# RiskChemi_Sensors_V2_03.net
KiCad netlist of a schematic drawn in Altium Designer
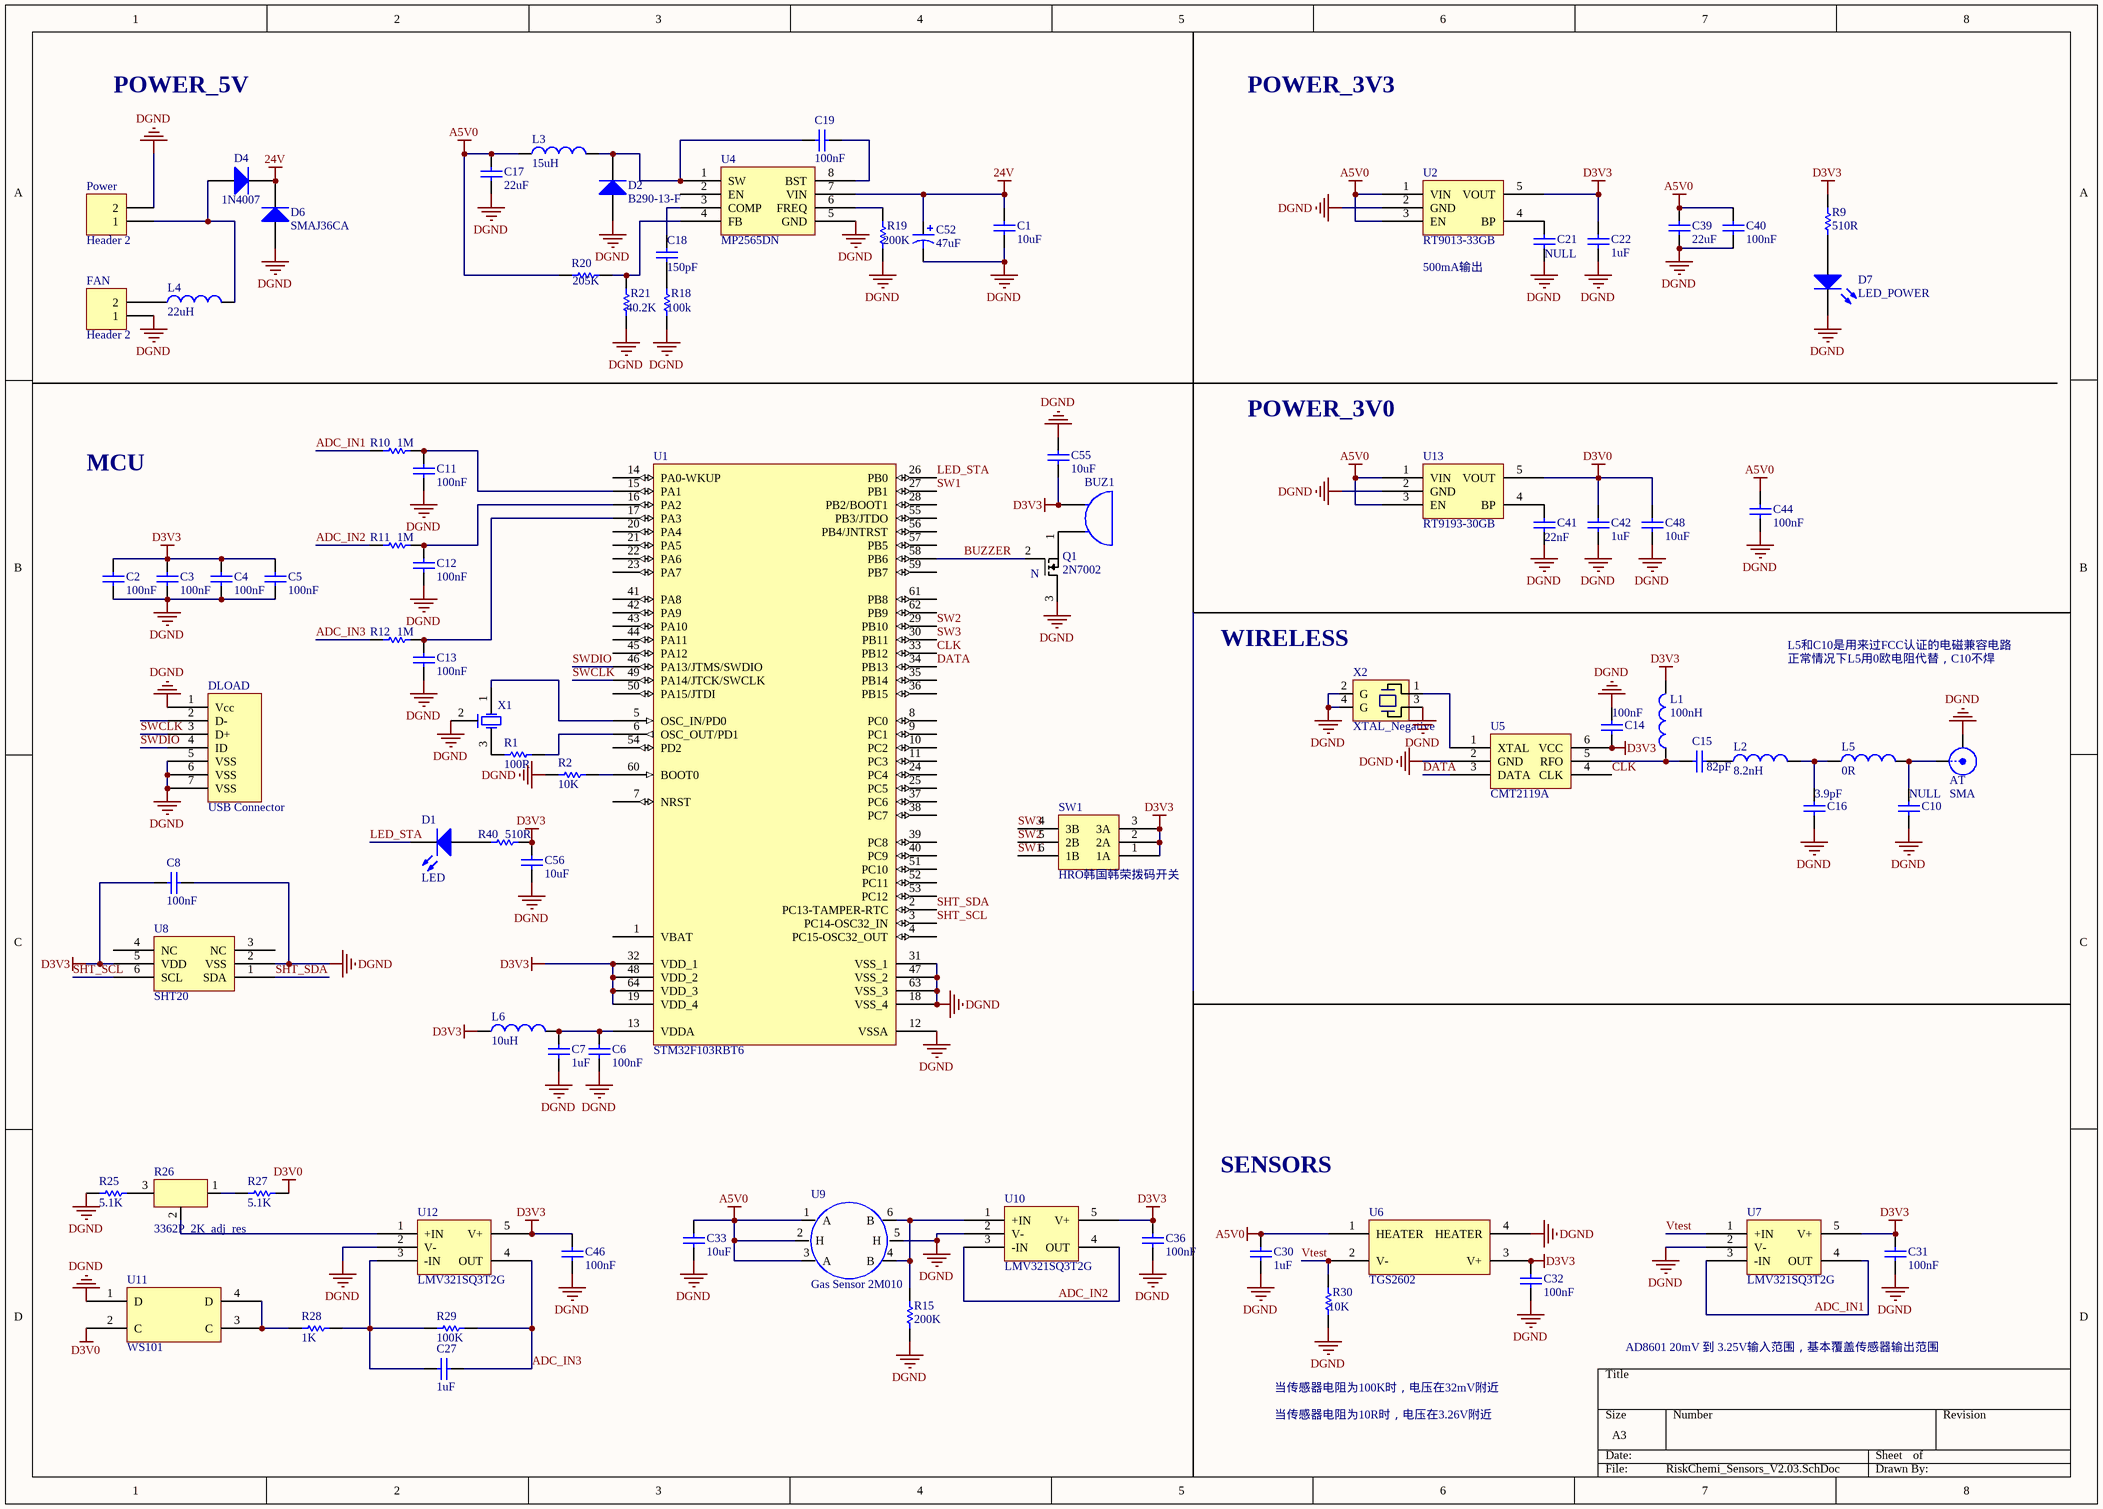
[diagram p0: RiskChemi_Sensors_V2.03.SchDoc]

(export (version "E")
  (design (tool "Eeschema 10.0.6"))
  (components
    (comp (ref "AT")
      (value "SMA")
      (footprint "SMA")
      (description "SMB Straight Connector")
      (fields (field (name "PUBLISHER") "Altium Limited"))
      (libsource (lib "Miscellaneous Connectors") (part "SMB"))
    )
    (comp (ref "BUZ1")
      (value "BUZZER 0905 through hole")
      (footprint "BUZ0905")
      (description "Buzzer")
      (libsource (lib "杂元件库") (part "BUZZER"))
    )
    (comp (ref "C1")
      (value "10uF")
      (footprint "0805")
      (description "Capacitor,50V")
      (fields (field (name "PUBLISHER") "Altium Limited"))
      (libsource (lib "Miscellaneous Devices") (part "Cap"))
    )
    (comp (ref "C2")
      (value "100nF")
      (footprint "BinFeng:0603")
      (description "Capacitor")
      (fields (field (name "PUBLISHER") "Altium Limited"))
      (libsource (lib "Miscellaneous Devices") (part "Cap"))
    )
    (comp (ref "C3")
      (value "100nF")
      (footprint "BinFeng:0603")
      (description "Capacitor")
      (fields (field (name "PUBLISHER") "Altium Limited"))
      (libsource (lib "Miscellaneous Devices") (part "Cap"))
    )
    (comp (ref "C4")
      (value "100nF")
      (footprint "BinFeng:0603")
      (description "Capacitor")
      (fields (field (name "PUBLISHER") "Altium Limited"))
      (libsource (lib "Miscellaneous Devices") (part "Cap"))
    )
    (comp (ref "C5")
      (value "100nF")
      (footprint "BinFeng:0603")
      (description "Capacitor")
      (fields (field (name "PUBLISHER") "Altium Limited"))
      (libsource (lib "Miscellaneous Devices") (part "Cap"))
    )
    (comp (ref "C6")
      (value "100nF")
      (footprint "BinFeng:0603")
      (description "Capacitor")
      (fields (field (name "PUBLISHER") "Altium Limited"))
      (libsource (lib "Miscellaneous Devices") (part "Cap"))
    )
    (comp (ref "C7")
      (value "1uF")
      (footprint "BinFeng:0603")
      (description "Capacitor")
      (fields (field (name "PUBLISHER") "Altium Limited"))
      (libsource (lib "Miscellaneous Devices") (part "Cap"))
    )
    (comp (ref "C8")
      (value "100nF")
      (footprint "BinFeng:0603")
      (description "Capacitor")
      (fields (field (name "PUBLISHER") "Altium Limited"))
      (libsource (lib "Miscellaneous Devices") (part "Cap"))
    )
    (comp (ref "C10")
      (value "NULL")
      (footprint "BinFeng:0402")
      (description "Capacitor")
      (fields (field (name "PUBLISHER") "Altium Limited"))
      (libsource (lib "Miscellaneous Devices") (part "Cap"))
    )
    (comp (ref "C11")
      (value "100nF")
      (footprint "BinFeng:0603")
      (description "Capacitor")
      (fields (field (name "PUBLISHER") "Altium Limited"))
      (libsource (lib "Miscellaneous Devices") (part "Cap"))
    )
    (comp (ref "C12")
      (value "100nF")
      (footprint "BinFeng:0603")
      (description "Capacitor")
      (fields (field (name "PUBLISHER") "Altium Limited"))
      (libsource (lib "Miscellaneous Devices") (part "Cap"))
    )
    (comp (ref "C13")
      (value "100nF")
      (footprint "BinFeng:0603")
      (description "Capacitor")
      (fields (field (name "PUBLISHER") "Altium Limited"))
      (libsource (lib "Miscellaneous Devices") (part "Cap"))
    )
    (comp (ref "C14")
      (value "100nF")
      (footprint "BinFeng:0402")
      (description "Capacitor")
      (fields (field (name "PUBLISHER") "Altium Limited"))
      (libsource (lib "Miscellaneous Devices") (part "Cap"))
    )
    (comp (ref "C15")
      (value "82pF")
      (footprint "BinFeng:0402")
      (description "Capacitor")
      (fields (field (name "PUBLISHER") "Altium Limited"))
      (libsource (lib "Miscellaneous Devices") (part "Cap"))
    )
    (comp (ref "C16")
      (value "3.9pF")
      (footprint "BinFeng:0402")
      (description "Capacitor")
      (fields (field (name "PUBLISHER") "Altium Limited"))
      (libsource (lib "Miscellaneous Devices") (part "Cap"))
    )
    (comp (ref "C17")
      (value "22uF")
      (footprint "0805")
      (description "Capacitor,50V")
      (fields (field (name "PUBLISHER") "Altium Limited"))
      (libsource (lib "Miscellaneous Devices") (part "Cap"))
    )
    (comp (ref "C18")
      (value "150pF")
      (footprint "BinFeng:0603")
      (description "Capacitor")
      (fields (field (name "PUBLISHER") "Altium Limited"))
      (libsource (lib "Miscellaneous Devices") (part "Cap"))
    )
    (comp (ref "C19")
      (value "100nF")
      (footprint "BinFeng:0603")
      (description "Capacitor")
      (fields (field (name "PUBLISHER") "Altium Limited"))
      (libsource (lib "Miscellaneous Devices") (part "Cap"))
    )
    (comp (ref "C21")
      (value "NULL")
      (footprint "BinFeng:0402")
      (description "Capacitor")
      (fields (field (name "PUBLISHER") "Altium Limited"))
      (libsource (lib "Miscellaneous Devices") (part "Cap"))
    )
    (comp (ref "C22")
      (value "1uF")
      (footprint "BinFeng:0402")
      (description "Capacitor")
      (fields (field (name "PUBLISHER") "Altium Limited"))
      (libsource (lib "Miscellaneous Devices") (part "Cap"))
    )
    (comp (ref "C27")
      (value "1uF")
      (footprint "BinFeng:0603")
      (description "Capacitor")
      (fields (field (name "PUBLISHER") "Altium Limited"))
      (libsource (lib "Miscellaneous Devices") (part "Cap"))
    )
    (comp (ref "C30")
      (value "1uF")
      (footprint "BinFeng:0603")
      (description "Capacitor")
      (fields (field (name "PUBLISHER") "Altium Limited"))
      (libsource (lib "Miscellaneous Devices") (part "Cap"))
    )
    (comp (ref "C31")
      (value "100nF")
      (footprint "BinFeng:0603")
      (description "Capacitor")
      (fields (field (name "PUBLISHER") "Altium Limited"))
      (libsource (lib "Miscellaneous Devices") (part "Cap"))
    )
    (comp (ref "C32")
      (value "100nF")
      (footprint "BinFeng:0603")
      (description "Capacitor")
      (fields (field (name "PUBLISHER") "Altium Limited"))
      (libsource (lib "Miscellaneous Devices") (part "Cap"))
    )
    (comp (ref "C33")
      (value "10uF")
      (footprint "0805")
      (description "Capacitor")
      (fields (field (name "PUBLISHER") "Altium Limited"))
      (libsource (lib "Miscellaneous Devices") (part "Cap"))
    )
    (comp (ref "C36")
      (value "100nF")
      (footprint "BinFeng:0603")
      (description "Capacitor")
      (fields (field (name "PUBLISHER") "Altium Limited"))
      (libsource (lib "Miscellaneous Devices") (part "Cap"))
    )
    (comp (ref "C39")
      (value "22uF")
      (footprint "1206")
      (description "Capacitor")
      (fields (field (name "PUBLISHER") "Altium Limited"))
      (libsource (lib "Miscellaneous Devices") (part "Cap"))
    )
    (comp (ref "C40")
      (value "100nF")
      (footprint "BinFeng:0402")
      (description "Capacitor")
      (fields (field (name "PUBLISHER") "Altium Limited"))
      (libsource (lib "Miscellaneous Devices") (part "Cap"))
    )
    (comp (ref "C41")
      (value "22nF")
      (footprint "BinFeng:0402")
      (description "Capacitor")
      (fields (field (name "PUBLISHER") "Altium Limited"))
      (libsource (lib "Miscellaneous Devices") (part "Cap"))
    )
    (comp (ref "C42")
      (value "1uF")
      (footprint "BinFeng:0402")
      (description "Capacitor")
      (fields (field (name "PUBLISHER") "Altium Limited"))
      (libsource (lib "Miscellaneous Devices") (part "Cap"))
    )
    (comp (ref "C44")
      (value "100nF")
      (footprint "BinFeng:0402")
      (description "Capacitor")
      (fields (field (name "PUBLISHER") "Altium Limited"))
      (libsource (lib "Miscellaneous Devices") (part "Cap"))
    )
    (comp (ref "C46")
      (value "100nF")
      (footprint "BinFeng:0603")
      (description "Capacitor")
      (fields (field (name "PUBLISHER") "Altium Limited"))
      (libsource (lib "Miscellaneous Devices") (part "Cap"))
    )
    (comp (ref "C48")
      (value "10uF")
      (footprint "0805")
      (description "Capacitor")
      (fields (field (name "PUBLISHER") "Altium Limited"))
      (libsource (lib "Miscellaneous Devices") (part "Cap"))
    )
    (comp (ref "C52")
      (value "47uF")
      (footprint "cap_pol_8*10.2")
      (description "Polarized Capacitor (Radial)")
      (fields (field (name "PUBLISHER") "Altium Limited"))
      (libsource (lib "Miscellaneous Devices") (part "Cap Pol1"))
    )
    (comp (ref "C55")
      (value "10uF")
      (footprint "0805")
      (description "Capacitor")
      (fields (field (name "PUBLISHER") "Altium Limited"))
      (libsource (lib "Miscellaneous Devices") (part "Cap"))
    )
    (comp (ref "C56")
      (value "10uF")
      (footprint "0805")
      (description "Capacitor")
      (fields (field (name "PUBLISHER") "Altium Limited"))
      (libsource (lib "Miscellaneous Devices") (part "Cap"))
    )
    (comp (ref "D1")
      (value "LED")
      (footprint "1206_LED")
      (description "Typical INFRARED GaAs LED")
      (fields (field (name "PUBLISHER") "Altium Limited"))
      (libsource (lib "Miscellaneous Devices") (part "LED0"))
    )
    (comp (ref "D2")
      (value "B290-13-F")
      (footprint "B290")
      (description "Default Diode")
      (fields (field (name "PUBLISHER") "Altium Limited"))
      (libsource (lib "Miscellaneous Devices") (part "Diode"))
    )
    (comp (ref "D4")
      (value "1N4007")
      (footprint "6032_pol")
      (description "1 Amp General Purpose Rectifier")
      (fields (field (name "PUBLISHER") "Altium Limited"))
      (libsource (lib "Miscellaneous Devices") (part "Diode 1N4007"))
    )
    (comp (ref "D6")
      (value "SMAJ36CA")
      (footprint "B290")
      (description "1 Amp General Purpose Rectifier")
      (fields (field (name "PUBLISHER") "Altium Limited"))
      (libsource (lib "Miscellaneous Devices") (part "Diode 1N4007"))
    )
    (comp (ref "D7")
      (value "LED_POWER")
      (footprint "1206_LED")
      (description "Typical INFRARED GaAs LED")
      (fields (field (name "PUBLISHER") "Altium Limited"))
      (libsource (lib "Miscellaneous Devices") (part "LED0"))
    )
    (comp (ref "DLOAD")
      (value "USB Connector")
      (footprint "Mini_USB")
      (libsource (lib "BinFeng_Connectors") (part "Component_1"))
    )
    (comp (ref "FAN")
      (value "Header 2")
      (footprint "HDR1X2")
      (description "Header, 2-Pin")
      (fields (field (name "PUBLISHER") "Altium Limited"))
      (libsource (lib "Miscellaneous Connectors") (part "Header 2"))
    )
    (comp (ref "L1")
      (value "100nH")
      (footprint "0603C")
      (description "Inductor")
      (fields (field (name "PUBLISHER") "Altium Limited"))
      (libsource (lib "Miscellaneous Devices") (part "Inductor"))
    )
    (comp (ref "L2")
      (value "8.2nH")
      (footprint "0603C")
      (description "Inductor")
      (fields (field (name "PUBLISHER") "Altium Limited"))
      (libsource (lib "Miscellaneous Devices") (part "Inductor"))
    )
    (comp (ref "L3")
      (value "15uH")
      (footprint "4*4 Inductor")
      (description "Inductor, 1A")
      (fields (field (name "PUBLISHER") "Altium Limited"))
      (libsource (lib "Miscellaneous Devices") (part "Inductor"))
    )
    (comp (ref "L4")
      (value "22uH")
      (footprint "10*10Inductor")
      (description "Inductor, 1A")
      (fields (field (name "PUBLISHER") "Altium Limited"))
      (libsource (lib "Miscellaneous Devices") (part "Inductor"))
    )
    (comp (ref "L5")
      (value "0R")
      (footprint "0603C")
      (description "Inductor")
      (fields (field (name "PUBLISHER") "Altium Limited"))
      (libsource (lib "Miscellaneous Devices") (part "Inductor"))
    )
    (comp (ref "L6")
      (value "10uH")
      (footprint "0805")
      (description "Inductor")
      (fields (field (name "PUBLISHER") "Altium Limited"))
      (libsource (lib "Miscellaneous Devices") (part "Inductor"))
    )
    (comp (ref "Power")
      (value "Header 2")
      (footprint "HDR1X2")
      (description "Header, 2-Pin")
      (fields (field (name "PUBLISHER") "Altium Limited"))
      (libsource (lib "Miscellaneous Connectors") (part "Header 2"))
    )
    (comp (ref "Q1") (value "2N7002") (footprint "2N7002") (libsource (lib "seeder") (part "N-MOSFET")))
    (comp (ref "R1")
      (value "100R")
      (footprint "BinFeng:0603")
      (description "Resistor")
      (fields (field (name "PUBLISHER") "Altium Limited"))
      (libsource (lib "Miscellaneous Devices") (part "Res1"))
    )
    (comp (ref "R2")
      (value "10K")
      (footprint "BinFeng:0603")
      (description "Resistor")
      (fields (field (name "PUBLISHER") "Altium Limited"))
      (libsource (lib "Miscellaneous Devices") (part "Res1"))
    )
    (comp (ref "R9")
      (value "510R")
      (footprint "BinFeng:0603")
      (description "Resistor")
      (fields (field (name "PUBLISHER") "Altium Limited"))
      (libsource (lib "Miscellaneous Devices") (part "Res1"))
    )
    (comp (ref "R10")
      (value "1M")
      (footprint "BinFeng:0603")
      (description "Resistor")
      (fields (field (name "PUBLISHER") "Altium Limited"))
      (libsource (lib "Miscellaneous Devices") (part "Res1"))
    )
    (comp (ref "R11")
      (value "1M")
      (footprint "BinFeng:0603")
      (description "Resistor")
      (fields (field (name "PUBLISHER") "Altium Limited"))
      (libsource (lib "Miscellaneous Devices") (part "Res1"))
    )
    (comp (ref "R12")
      (value "1M")
      (footprint "BinFeng:0603")
      (description "Resistor")
      (fields (field (name "PUBLISHER") "Altium Limited"))
      (libsource (lib "Miscellaneous Devices") (part "Res1"))
    )
    (comp (ref "R15")
      (value "200K")
      (footprint "BinFeng:0603C")
      (description "Resistor")
      (fields (field (name "Comment") "Res1") (field (name "PUBLISHER") "Altium Limited"))
      (libsource (lib "Miscellaneous Devices") (part "Res1"))
    )
    (comp (ref "R18")
      (value "100k")
      (footprint "BinFeng:0603")
      (description "Resistor")
      (fields (field (name "PUBLISHER") "Altium Limited"))
      (libsource (lib "Miscellaneous Devices") (part "Res1"))
    )
    (comp (ref "R19")
      (value "200K")
      (footprint "BinFeng:0402")
      (description "Resistor")
      (fields (field (name "PUBLISHER") "Altium Limited"))
      (libsource (lib "Miscellaneous Devices") (part "Res1"))
    )
    (comp (ref "R20")
      (value "205K")
      (footprint "BinFeng:0603")
      (description "Resistor")
      (fields (field (name "PUBLISHER") "Altium Limited"))
      (libsource (lib "Miscellaneous Devices") (part "Res1"))
    )
    (comp (ref "R21")
      (value "40.2K")
      (footprint "BinFeng:0603")
      (description "Resistor")
      (fields (field (name "PUBLISHER") "Altium Limited"))
      (libsource (lib "Miscellaneous Devices") (part "Res1"))
    )
    (comp (ref "R25")
      (value "5.1K")
      (footprint "BinFeng:0603")
      (description "Resistor")
      (fields (field (name "PUBLISHER") "Altium Limited"))
      (libsource (lib "Miscellaneous Devices") (part "Res1"))
    )
    (comp (ref "R26")
      (value "3362P_2K_adj_res")
      (footprint "res_adj")
      (libsource (lib "BinFeng_IC") (part "res_adj"))
    )
    (comp (ref "R27")
      (value "5.1K")
      (footprint "BinFeng:0603")
      (description "Resistor")
      (fields (field (name "PUBLISHER") "Altium Limited"))
      (libsource (lib "Miscellaneous Devices") (part "Res1"))
    )
    (comp (ref "R28")
      (value "1K")
      (footprint "BinFeng:0603")
      (description "Resistor")
      (fields (field (name "PUBLISHER") "Altium Limited"))
      (libsource (lib "Miscellaneous Devices") (part "Res1"))
    )
    (comp (ref "R29")
      (value "100K")
      (footprint "BinFeng:0603")
      (description "Resistor")
      (fields (field (name "PUBLISHER") "Altium Limited"))
      (libsource (lib "Miscellaneous Devices") (part "Res1"))
    )
    (comp (ref "R30")
      (value "10K")
      (footprint "BinFeng:0603")
      (description "Resistor")
      (fields (field (name "PUBLISHER") "Altium Limited"))
      (libsource (lib "Miscellaneous Devices") (part "Res1"))
    )
    (comp (ref "R40")
      (value "510R")
      (footprint "BinFeng:0603")
      (description "Resistor")
      (fields (field (name "PUBLISHER") "Altium Limited"))
      (libsource (lib "Miscellaneous Devices") (part "Res1"))
    )
    (comp (ref "SW1")
      (value "HRO韩国韩荣拨码开关")
      (footprint "SW_6P_HRO")
      (libsource (lib "BinFeng_IC") (part "SW_6P"))
    )
    (comp (ref "U1")
      (value "STM32F103RBT6")
      (footprint "LQFP64_N")
      (description "STM32 ARM-based 32-bit MCU with 64 Kbytes Flash, 64-pin LQFP, Industrial Temperature")
      (fields (field (name "PUBLISHER") "Altium Limited"))
      (libsource (lib "ST Microcontroller 32-Bit STM32") (part "STM32F103R8T6"))
    )
    (comp (ref "U2")
      (value "RT9013-33GB")
      (footprint "SOT-23-5")
      (libsource (lib "BinFeng_IC") (part "RT9193"))
    )
    (comp (ref "U4")
      (value "MP2565DN")
      (footprint "so-8")
      (description "DCDC 4.5V~28V input 1.8V ~5V output low power")
      (libsource (lib "BinFeng_IC") (part "MP1584"))
    )
    (comp (ref "U5")
      (value "CMT2119A")
      (footprint "sot23-6")
      (libsource (lib "BinFeng_IC") (part "CMT2119A"))
    )
    (comp (ref "U6")
      (value "TGS2602")
      (footprint "Gas Sensor TGS2602 Slot")
      (description "VOC sensor")
      (libsource (lib "BinFeng_IC") (part "TGS2602"))
    )
    (comp (ref "U7")
      (value "LMV321SQ3T2G")
      (footprint "SC-70-5")
      (libsource (lib "BinFeng_IC") (part "LMV321SQ3T2G"))
    )
    (comp (ref "U8") (value "SHT20") (footprint "SHT20") (libsource (lib "BinFeng_IC") (part "SHT20")))
    (comp (ref "U9")
      (value "Gas Sensor 2M010")
      (footprint "Gas Sensor 2M010 Slot")
      (libsource (lib "BinFeng_IC") (part "Gas Sensor"))
    )
    (comp (ref "U10")
      (value "LMV321SQ3T2G")
      (footprint "SC-70-5")
      (libsource (lib "BinFeng_IC") (part "LMV321SQ3T2G"))
    )
    (comp (ref "U11")
      (value "WS101")
      (footprint "Gas_Sensor_WS101_Slot")
      (libsource (lib "BinFeng_IC") (part "Gas Sensor_WS101"))
    )
    (comp (ref "U12")
      (value "LMV321SQ3T2G")
      (footprint "SC-70-5")
      (libsource (lib "BinFeng_IC") (part "LMV321SQ3T2G"))
    )
    (comp (ref "U13")
      (value "RT9193-30GB")
      (footprint "SOT-23-5")
      (libsource (lib "BinFeng_IC") (part "RT9193"))
    )
    (comp (ref "X1") (value "8M smd") (footprint "8Mhz_XTAL") (libsource (lib "Schlib1") (part "8M smd")))
    (comp (ref "X2")
      (value "XTAL_Negative")
      (footprint "XTAL3225")
      (libsource (lib "BinFeng_IC") (part "XTAL_Negative"))
    )
  )
  (nets
    (net (code "1") (name "/ADC_IN1") (class "Default")
      (node (ref "R10") (pin "1") (pinfunction "1_1") (pintype "passive"))
      (node (ref "U7") (pin "3") (pinfunction "-IN_3") (pintype "passive"))
      (node (ref "U7") (pin "4") (pinfunction "OUT_4") (pintype "passive"))
    )
    (net (code "2") (name "/ADC_IN2") (class "Default")
      (node (ref "R11") (pin "1") (pinfunction "1_1") (pintype "passive"))
      (node (ref "U10") (pin "3") (pinfunction "-IN_3") (pintype "passive"))
      (node (ref "U10") (pin "4") (pinfunction "OUT_4") (pintype "passive"))
    )
    (net (code "3") (name "/ADC_IN3") (class "Default")
      (node (ref "C27") (pin "1") (pinfunction "1_1") (pintype "passive"))
      (node (ref "R12") (pin "1") (pinfunction "1_1") (pintype "passive"))
      (node (ref "R29") (pin "2") (pinfunction "2_2") (pintype "passive"))
      (node (ref "U12") (pin "4") (pinfunction "OUT_4") (pintype "passive"))
    )
    (net (code "4") (name "/BUZZER") (class "Default")
      (node (ref "Q1") (pin "2") (pinfunction "G_2") (pintype "passive"))
      (node (ref "U1") (pin "58") (pinfunction "PB6_58") (pintype "bidirectional"))
    )
    (net (code "5") (name "/CLK") (class "Default")
      (node (ref "U1") (pin "33") (pinfunction "PB12_33") (pintype "bidirectional"))
      (node (ref "U5") (pin "4") (pinfunction "CLK_4") (pintype "passive"))
    )
    (net (code "6") (name "/DATA") (class "Default")
      (node (ref "U1") (pin "34") (pinfunction "PB13_34") (pintype "bidirectional"))
      (node (ref "U5") (pin "3") (pinfunction "DATA_3") (pintype "passive"))
    )
    (net (code "7") (name "/LED_STA") (class "Default")
      (node (ref "D1") (pin "2") (pinfunction "K_2") (pintype "passive"))
      (node (ref "U1") (pin "26") (pinfunction "PB0_26") (pintype "bidirectional"))
    )
    (net (code "8") (name "/SHT_SCL") (class "Default")
      (node (ref "U1") (pin "3") (pinfunction "PC14-OSC32_IN_3") (pintype "bidirectional"))
      (node (ref "U8") (pin "6") (pinfunction "SCL_6") (pintype "passive"))
    )
    (net (code "9") (name "/SHT_SDA") (class "Default")
      (node (ref "U1") (pin "2") (pinfunction "PC13-TAMPER-RTC_2") (pintype "bidirectional"))
      (node (ref "U8") (pin "1") (pinfunction "SDA_1") (pintype "passive"))
    )
    (net (code "10") (name "/SW1") (class "Default")
      (node (ref "SW1") (pin "6") (pinfunction "1B_6") (pintype "passive"))
      (node (ref "U1") (pin "27") (pinfunction "PB1_27") (pintype "bidirectional"))
    )
    (net (code "11") (name "/SW2") (class "Default")
      (node (ref "SW1") (pin "5") (pinfunction "2B_5") (pintype "passive"))
      (node (ref "U1") (pin "29") (pinfunction "PB10_29") (pintype "bidirectional"))
    )
    (net (code "12") (name "/SW3") (class "Default")
      (node (ref "SW1") (pin "4") (pinfunction "3B_4") (pintype "passive"))
      (node (ref "U1") (pin "30") (pinfunction "PB11_30") (pintype "bidirectional"))
    )
    (net (code "13") (name "/SWCLK") (class "Default")
      (node (ref "DLOAD") (pin "3") (pinfunction "D+_3") (pintype "passive"))
      (node (ref "U1") (pin "49") (pinfunction "PA14/JTCK/SWCLK_49") (pintype "bidirectional"))
    )
    (net (code "14") (name "/SWDIO") (class "Default")
      (node (ref "DLOAD") (pin "4") (pinfunction "ID_4") (pintype "passive"))
      (node (ref "U1") (pin "46") (pinfunction "PA13/JTMS/SWDIO_46") (pintype "bidirectional"))
    )
    (net (code "15") (name "/Vtest") (class "Default")
      (node (ref "R30") (pin "2") (pinfunction "2_2") (pintype "passive"))
      (node (ref "U6") (pin "2") (pinfunction "V-_2") (pintype "passive"))
      (node (ref "U7") (pin "1") (pinfunction "+IN_1") (pintype "passive"))
    )
    (net (code "16") (name "24V") (class "Default")
      (node (ref "C1") (pin "2") (pinfunction "2_2") (pintype "passive"))
      (node (ref "C52") (pin "1") (pinfunction "1_1") (pintype "passive"))
      (node (ref "D4") (pin "2") (pinfunction "K_2") (pintype "passive"))
      (node (ref "D6") (pin "2") (pinfunction "K_2") (pintype "passive"))
      (node (ref "U4") (pin "7") (pinfunction "VIN_7") (pintype "passive"))
    )
    (net (code "17") (name "A5V0") (class "Default")
      (node (ref "C17") (pin "2") (pinfunction "2_2") (pintype "passive"))
      (node (ref "C30") (pin "2") (pinfunction "2_2") (pintype "passive"))
      (node (ref "C33") (pin "2") (pinfunction "2_2") (pintype "passive"))
      (node (ref "C39") (pin "1") (pinfunction "1_1") (pintype "passive"))
      (node (ref "C40") (pin "2") (pinfunction "2_2") (pintype "passive"))
      (node (ref "C44") (pin "2") (pinfunction "2_2") (pintype "passive"))
      (node (ref "L3") (pin "1") (pinfunction "1_1") (pintype "passive"))
      (node (ref "R20") (pin "2") (pinfunction "2_2") (pintype "passive"))
      (node (ref "U13") (pin "1") (pinfunction "VIN_1") (pintype "passive"))
      (node (ref "U13") (pin "3") (pinfunction "EN_3") (pintype "passive"))
      (node (ref "U2") (pin "1") (pinfunction "VIN_1") (pintype "passive"))
      (node (ref "U2") (pin "3") (pinfunction "EN_3") (pintype "passive"))
      (node (ref "U6") (pin "1") (pinfunction "HEATER_1") (pintype "passive"))
      (node (ref "U9") (pin "1") (pinfunction "A_1") (pintype "passive"))
      (node (ref "U9") (pin "2") (pinfunction "H_2") (pintype "passive"))
      (node (ref "U9") (pin "3") (pinfunction "A_3") (pintype "passive"))
    )
    (net (code "18") (name "D3V0") (class "Default")
      (node (ref "C42") (pin "2") (pinfunction "2_2") (pintype "passive"))
      (node (ref "C48") (pin "2") (pinfunction "2_2") (pintype "passive"))
      (node (ref "R27") (pin "2") (pinfunction "2_2") (pintype "passive"))
      (node (ref "U11") (pin "2") (pinfunction "C_2") (pintype "passive"))
      (node (ref "U13") (pin "5") (pinfunction "VOUT_5") (pintype "passive"))
    )
    (net (code "19") (name "D3V3") (class "Default")
      (node (ref "BUZ1") (pin "1") (pinfunction "A_1") (pintype "passive"))
      (node (ref "C14") (pin "2") (pinfunction "2_2") (pintype "passive"))
      (node (ref "C2") (pin "2") (pinfunction "2_2") (pintype "passive"))
      (node (ref "C22") (pin "2") (pinfunction "2_2") (pintype "passive"))
      (node (ref "C3") (pin "2") (pinfunction "2_2") (pintype "passive"))
      (node (ref "C31") (pin "2") (pinfunction "2_2") (pintype "passive"))
      (node (ref "C32") (pin "2") (pinfunction "2_2") (pintype "passive"))
      (node (ref "C36") (pin "2") (pinfunction "2_2") (pintype "passive"))
      (node (ref "C4") (pin "2") (pinfunction "2_2") (pintype "passive"))
      (node (ref "C46") (pin "2") (pinfunction "2_2") (pintype "passive"))
      (node (ref "C5") (pin "2") (pinfunction "2_2") (pintype "passive"))
      (node (ref "C55") (pin "2") (pinfunction "2_2") (pintype "passive"))
      (node (ref "C56") (pin "2") (pinfunction "2_2") (pintype "passive"))
      (node (ref "C8") (pin "2") (pinfunction "2_2") (pintype "passive"))
      (node (ref "L1") (pin "2") (pinfunction "2_2") (pintype "passive"))
      (node (ref "L6") (pin "1") (pinfunction "1_1") (pintype "passive"))
      (node (ref "R40") (pin "2") (pinfunction "2_2") (pintype "passive"))
      (node (ref "R9") (pin "2") (pinfunction "2_2") (pintype "passive"))
      (node (ref "SW1") (pin "1") (pinfunction "1A_1") (pintype "passive"))
      (node (ref "SW1") (pin "2") (pinfunction "2A_2") (pintype "passive"))
      (node (ref "SW1") (pin "3") (pinfunction "3A_3") (pintype "passive"))
      (node (ref "U1") (pin "19") (pinfunction "VDD_4_19") (pintype "power_in"))
      (node (ref "U1") (pin "32") (pinfunction "VDD_1_32") (pintype "power_in"))
      (node (ref "U1") (pin "48") (pinfunction "VDD_2_48") (pintype "power_in"))
      (node (ref "U1") (pin "64") (pinfunction "VDD_3_64") (pintype "power_in"))
      (node (ref "U10") (pin "5") (pinfunction "V+_5") (pintype "passive"))
      (node (ref "U12") (pin "5") (pinfunction "V+_5") (pintype "passive"))
      (node (ref "U2") (pin "5") (pinfunction "VOUT_5") (pintype "passive"))
      (node (ref "U5") (pin "6") (pinfunction "VCC_6") (pintype "passive"))
      (node (ref "U6") (pin "3") (pinfunction "V+_3") (pintype "passive"))
      (node (ref "U7") (pin "5") (pinfunction "V+_5") (pintype "passive"))
      (node (ref "U8") (pin "5") (pinfunction "VDD_5") (pintype "passive"))
    )
    (net (code "20") (name "DGND") (class "Default")
      (node (ref "AT") (pin "2") (pinfunction "Y_2") (pintype "passive"))
      (node (ref "C1") (pin "1") (pinfunction "1_1") (pintype "passive"))
      (node (ref "C10") (pin "1") (pinfunction "1_1") (pintype "passive"))
      (node (ref "C11") (pin "2") (pinfunction "2_2") (pintype "passive"))
      (node (ref "C12") (pin "1") (pinfunction "1_1") (pintype "passive"))
      (node (ref "C13") (pin "1") (pinfunction "1_1") (pintype "passive"))
      (node (ref "C14") (pin "1") (pinfunction "1_1") (pintype "passive"))
      (node (ref "C16") (pin "1") (pinfunction "1_1") (pintype "passive"))
      (node (ref "C17") (pin "1") (pinfunction "1_1") (pintype "passive"))
      (node (ref "C2") (pin "1") (pinfunction "1_1") (pintype "passive"))
      (node (ref "C21") (pin "1") (pinfunction "1_1") (pintype "passive"))
      (node (ref "C22") (pin "1") (pinfunction "1_1") (pintype "passive"))
      (node (ref "C3") (pin "1") (pinfunction "1_1") (pintype "passive"))
      (node (ref "C30") (pin "1") (pinfunction "1_1") (pintype "passive"))
      (node (ref "C31") (pin "1") (pinfunction "1_1") (pintype "passive"))
      (node (ref "C32") (pin "1") (pinfunction "1_1") (pintype "passive"))
      (node (ref "C33") (pin "1") (pinfunction "1_1") (pintype "passive"))
      (node (ref "C36") (pin "1") (pinfunction "1_1") (pintype "passive"))
      (node (ref "C39") (pin "2") (pinfunction "2_2") (pintype "passive"))
      (node (ref "C4") (pin "1") (pinfunction "1_1") (pintype "passive"))
      (node (ref "C40") (pin "1") (pinfunction "1_1") (pintype "passive"))
      (node (ref "C41") (pin "1") (pinfunction "1_1") (pintype "passive"))
      (node (ref "C42") (pin "1") (pinfunction "1_1") (pintype "passive"))
      (node (ref "C44") (pin "1") (pinfunction "1_1") (pintype "passive"))
      (node (ref "C46") (pin "1") (pinfunction "1_1") (pintype "passive"))
      (node (ref "C48") (pin "1") (pinfunction "1_1") (pintype "passive"))
      (node (ref "C5") (pin "1") (pinfunction "1_1") (pintype "passive"))
      (node (ref "C52") (pin "2") (pinfunction "2_2") (pintype "passive"))
      (node (ref "C55") (pin "1") (pinfunction "1_1") (pintype "passive"))
      (node (ref "C56") (pin "1") (pinfunction "1_1") (pintype "passive"))
      (node (ref "C6") (pin "1") (pinfunction "1_1") (pintype "passive"))
      (node (ref "C7") (pin "1") (pinfunction "1_1") (pintype "passive"))
      (node (ref "C8") (pin "1") (pinfunction "1_1") (pintype "passive"))
      (node (ref "D2") (pin "1") (pinfunction "A_1") (pintype "passive"))
      (node (ref "D6") (pin "1") (pinfunction "A_1") (pintype "passive"))
      (node (ref "D7") (pin "2") (pinfunction "K_2") (pintype "passive"))
      (node (ref "DLOAD") (pin "1") (pinfunction "Vcc_1") (pintype "passive"))
      (node (ref "DLOAD") (pin "5") (pinfunction "VSS_5") (pintype "passive"))
      (node (ref "DLOAD") (pin "6") (pinfunction "VSS_6") (pintype "passive"))
      (node (ref "DLOAD") (pin "7") (pinfunction "VSS_7") (pintype "passive"))
      (node (ref "FAN") (pin "1") (pinfunction "1_1") (pintype "passive"))
      (node (ref "Power") (pin "2") (pinfunction "2_2") (pintype "passive"))
      (node (ref "Q1") (pin "3") (pinfunction "S_3") (pintype "passive"))
      (node (ref "R15") (pin "2") (pinfunction "2_2") (pintype "passive"))
      (node (ref "R18") (pin "1") (pinfunction "1_1") (pintype "passive"))
      (node (ref "R19") (pin "1") (pinfunction "1_1") (pintype "passive"))
      (node (ref "R2") (pin "1") (pinfunction "1_1") (pintype "passive"))
      (node (ref "R21") (pin "1") (pinfunction "1_1") (pintype "passive"))
      (node (ref "R25") (pin "1") (pinfunction "1_1") (pintype "passive"))
      (node (ref "R30") (pin "1") (pinfunction "1_1") (pintype "passive"))
      (node (ref "U1") (pin "12") (pinfunction "VSSA_12") (pintype "power_in"))
      (node (ref "U1") (pin "18") (pinfunction "VSS_4_18") (pintype "power_in"))
      (node (ref "U1") (pin "31") (pinfunction "VSS_1_31") (pintype "power_in"))
      (node (ref "U1") (pin "47") (pinfunction "VSS_2_47") (pintype "power_in"))
      (node (ref "U1") (pin "63") (pinfunction "VSS_3_63") (pintype "power_in"))
      (node (ref "U10") (pin "2") (pinfunction "V-_2") (pintype "passive"))
      (node (ref "U11") (pin "1") (pinfunction "D_1") (pintype "passive"))
      (node (ref "U12") (pin "2") (pinfunction "V-_2") (pintype "passive"))
      (node (ref "U13") (pin "2") (pinfunction "GND_2") (pintype "passive"))
      (node (ref "U2") (pin "2") (pinfunction "GND_2") (pintype "passive"))
      (node (ref "U4") (pin "5") (pinfunction "GND_5") (pintype "passive"))
      (node (ref "U5") (pin "2") (pinfunction "GND_2") (pintype "passive"))
      (node (ref "U6") (pin "4") (pinfunction "HEATER_4") (pintype "passive"))
      (node (ref "U7") (pin "2") (pinfunction "V-_2") (pintype "passive"))
      (node (ref "U8") (pin "2") (pinfunction "VSS_2") (pintype "passive"))
      (node (ref "U9") (pin "5") (pinfunction "H_5") (pintype "passive"))
      (node (ref "X1") (pin "2") (pinfunction "GND_2") (pintype "passive"))
      (node (ref "X2") (pin "2") (pinfunction "G_2") (pintype "passive"))
      (node (ref "X2") (pin "3") (pintype "passive"))
      (node (ref "X2") (pin "4") (pinfunction "G_4") (pintype "passive"))
    )
    (net (code "21") (name "Net-(AT-X)") (class "Default")
      (node (ref "AT") (pin "1") (pinfunction "X_1") (pintype "passive"))
      (node (ref "C10") (pin "2") (pinfunction "2_2") (pintype "passive"))
      (node (ref "L5") (pin "2") (pinfunction "2_2") (pintype "passive"))
    )
    (net (code "22") (name "Net-(BUZ1-B)") (class "Default")
      (node (ref "BUZ1") (pin "2") (pinfunction "B_2") (pintype "passive"))
      (node (ref "Q1") (pin "1") (pinfunction "D_1") (pintype "passive"))
    )
    (net (code "23") (name "Net-(C15-Pad2)") (class "Default")
      (node (ref "C15") (pin "2") (pinfunction "2_2") (pintype "passive"))
      (node (ref "L2") (pin "1") (pinfunction "1_1") (pintype "passive"))
    )
    (net (code "24") (name "Net-(C16-Pad2)") (class "Default")
      (node (ref "C16") (pin "2") (pinfunction "2_2") (pintype "passive"))
      (node (ref "L2") (pin "2") (pinfunction "2_2") (pintype "passive"))
      (node (ref "L5") (pin "1") (pinfunction "1_1") (pintype "passive"))
    )
    (net (code "25") (name "Net-(C18-Pad2)") (class "Default")
      (node (ref "C18") (pin "2") (pinfunction "2_2") (pintype "passive"))
      (node (ref "R18") (pin "2") (pinfunction "2_2") (pintype "passive"))
    )
    (net (code "26") (name "Net-(D1-A)") (class "Default")
      (node (ref "D1") (pin "1") (pinfunction "A_1") (pintype "passive"))
      (node (ref "R40") (pin "1") (pinfunction "1_1") (pintype "passive"))
    )
    (net (code "27") (name "Net-(D2-K)") (class "Default")
      (node (ref "C19") (pin "2") (pinfunction "2_2") (pintype "passive"))
      (node (ref "D2") (pin "2") (pinfunction "K_2") (pintype "passive"))
      (node (ref "L3") (pin "2") (pinfunction "2_2") (pintype "passive"))
      (node (ref "U4") (pin "1") (pinfunction "SW_1") (pintype "passive"))
    )
    (net (code "28") (name "Net-(D4-A)") (class "Default")
      (node (ref "D4") (pin "1") (pinfunction "A_1") (pintype "passive"))
      (node (ref "L4") (pin "2") (pinfunction "2_2") (pintype "passive"))
      (node (ref "Power") (pin "1") (pinfunction "1_1") (pintype "passive"))
    )
    (net (code "29") (name "Net-(D7-A)") (class "Default")
      (node (ref "D7") (pin "1") (pinfunction "A_1") (pintype "passive"))
      (node (ref "R9") (pin "1") (pinfunction "1_1") (pintype "passive"))
    )
    (net (code "30") (name "Net-(FAN-Pad2)") (class "Default")
      (node (ref "FAN") (pin "2") (pinfunction "2_2") (pintype "passive"))
      (node (ref "L4") (pin "1") (pinfunction "1_1") (pintype "passive"))
    )
    (net (code "31") (name "Net-(R25-Pad2)") (class "Default")
      (node (ref "R25") (pin "2") (pinfunction "2_2") (pintype "passive"))
      (node (ref "R26") (pin "3") (pintype "passive"))
    )
    (net (code "32") (name "Net-(R26-Pad1)") (class "Default")
      (node (ref "R26") (pin "1") (pintype "passive"))
      (node (ref "R27") (pin "1") (pinfunction "1_1") (pintype "passive"))
    )
    (net (code "33") (name "Net-(R28-Pad1)") (class "Default")
      (node (ref "R28") (pin "1") (pinfunction "1_1") (pintype "passive"))
      (node (ref "U11") (pin "3") (pinfunction "C_3") (pintype "passive"))
      (node (ref "U11") (pin "4") (pinfunction "D_4") (pintype "passive"))
    )
    (net (code "34") (name "Net-(U1-BOOT0)") (class "Default")
      (node (ref "R2") (pin "2") (pinfunction "2_2") (pintype "passive"))
      (node (ref "U1") (pin "60") (pinfunction "BOOT0_60") (pintype "input"))
    )
    (net (code "35") (name "Net-(U1-OSC_IN{slash}PD0)") (class "Default")
      (node (ref "U1") (pin "5") (pinfunction "OSC_IN/PD0_5") (pintype "input"))
      (node (ref "X1") (pin "1") (pinfunction "OSC1_1") (pintype "passive"))
    )
    (net (code "36") (name "Net-(U1-OSC_OUT{slash}PD1)") (class "Default")
      (node (ref "R1") (pin "2") (pinfunction "2_2") (pintype "passive"))
      (node (ref "U1") (pin "6") (pinfunction "OSC_OUT/PD1_6") (pintype "output"))
    )
    (net (code "37") (name "Net-(U1-PA1)") (class "Default")
      (node (ref "C11") (pin "1") (pinfunction "1_1") (pintype "passive"))
      (node (ref "R10") (pin "2") (pinfunction "2_2") (pintype "passive"))
      (node (ref "U1") (pin "15") (pinfunction "PA1_15") (pintype "bidirectional"))
    )
    (net (code "38") (name "Net-(U1-PA2)") (class "Default")
      (node (ref "C12") (pin "2") (pinfunction "2_2") (pintype "passive"))
      (node (ref "R11") (pin "2") (pinfunction "2_2") (pintype "passive"))
      (node (ref "U1") (pin "16") (pinfunction "PA2_16") (pintype "bidirectional"))
    )
    (net (code "39") (name "Net-(U1-PA3)") (class "Default")
      (node (ref "C13") (pin "2") (pinfunction "2_2") (pintype "passive"))
      (node (ref "R12") (pin "2") (pinfunction "2_2") (pintype "passive"))
      (node (ref "U1") (pin "17") (pinfunction "PA3_17") (pintype "bidirectional"))
    )
    (net (code "40") (name "Net-(U1-VDDA)") (class "Default")
      (node (ref "C6") (pin "2") (pinfunction "2_2") (pintype "passive"))
      (node (ref "C7") (pin "2") (pinfunction "2_2") (pintype "passive"))
      (node (ref "L6") (pin "2") (pinfunction "2_2") (pintype "passive"))
      (node (ref "U1") (pin "13") (pinfunction "VDDA_13") (pintype "power_in"))
    )
    (net (code "41") (name "Net-(U2-BP)") (class "Default")
      (node (ref "C21") (pin "2") (pinfunction "2_2") (pintype "passive"))
      (node (ref "U2") (pin "4") (pinfunction "BP_4") (pintype "passive"))
    )
    (net (code "42") (name "Net-(U4-BST)") (class "Default")
      (node (ref "C19") (pin "1") (pinfunction "1_1") (pintype "passive"))
      (node (ref "U4") (pin "8") (pinfunction "BST_8") (pintype "passive"))
    )
    (net (code "43") (name "Net-(U4-COMP)") (class "Default")
      (node (ref "C18") (pin "1") (pinfunction "1_1") (pintype "passive"))
      (node (ref "U4") (pin "3") (pinfunction "COMP_3") (pintype "passive"))
    )
    (net (code "44") (name "Net-(U4-FB)") (class "Default")
      (node (ref "R20") (pin "1") (pinfunction "1_1") (pintype "passive"))
      (node (ref "R21") (pin "2") (pinfunction "2_2") (pintype "passive"))
      (node (ref "U4") (pin "4") (pinfunction "FB_4") (pintype "passive"))
    )
    (net (code "45") (name "Net-(U4-FREQ)") (class "Default")
      (node (ref "R19") (pin "2") (pinfunction "2_2") (pintype "passive"))
      (node (ref "U4") (pin "6") (pinfunction "FREQ_6") (pintype "passive"))
    )
    (net (code "46") (name "Net-(U5-RFO)") (class "Default")
      (node (ref "C15") (pin "1") (pinfunction "1_1") (pintype "passive"))
      (node (ref "L1") (pin "1") (pinfunction "1_1") (pintype "passive"))
      (node (ref "U5") (pin "5") (pinfunction "RFO_5") (pintype "passive"))
    )
    (net (code "47") (name "Net-(U5-XTAL)") (class "Default")
      (node (ref "U5") (pin "1") (pinfunction "XTAL_1") (pintype "passive"))
      (node (ref "X2") (pin "1") (pintype "passive"))
    )
    (net (code "48") (name "Net-(U10-+IN)") (class "Default")
      (node (ref "R15") (pin "1") (pinfunction "1_1") (pintype "passive"))
      (node (ref "U10") (pin "1") (pinfunction "+IN_1") (pintype "passive"))
      (node (ref "U9") (pin "4") (pinfunction "B_4") (pintype "passive"))
      (node (ref "U9") (pin "6") (pinfunction "B_6") (pintype "passive"))
    )
    (net (code "49") (name "Net-(U12-+IN)") (class "Default")
      (node (ref "R26") (pin "2") (pintype "passive"))
      (node (ref "U12") (pin "1") (pinfunction "+IN_1") (pintype "passive"))
    )
    (net (code "50") (name "Net-(U12--IN)") (class "Default")
      (node (ref "C27") (pin "2") (pinfunction "2_2") (pintype "passive"))
      (node (ref "R28") (pin "2") (pinfunction "2_2") (pintype "passive"))
      (node (ref "R29") (pin "1") (pinfunction "1_1") (pintype "passive"))
      (node (ref "U12") (pin "3") (pinfunction "-IN_3") (pintype "passive"))
    )
    (net (code "51") (name "Net-(U13-BP)") (class "Default")
      (node (ref "C41") (pin "2") (pinfunction "2_2") (pintype "passive"))
      (node (ref "U13") (pin "4") (pinfunction "BP_4") (pintype "passive"))
    )
    (net (code "52") (name "Net-(X1-OSC2)") (class "Default")
      (node (ref "R1") (pin "1") (pinfunction "1_1") (pintype "passive"))
      (node (ref "X1") (pin "3") (pinfunction "OSC2_3") (pintype "passive"))
    )
    (net (code "53") (name "unconnected-(DLOAD-D--Pad2)") (class "Default")
      (node (ref "DLOAD") (pin "2") (pinfunction "D-_2") (pintype "passive"))
    )
    (net (code "54") (name "unconnected-(U1-NRST-Pad7)") (class "Default")
      (node (ref "U1") (pin "7") (pinfunction "NRST_7") (pintype "bidirectional"))
    )
    (net (code "55") (name "unconnected-(U1-PA0-WKUP-Pad14)") (class "Default")
      (node (ref "U1") (pin "14") (pinfunction "PA0-WKUP_14") (pintype "bidirectional"))
    )
    (net (code "56") (name "unconnected-(U1-PA4-Pad20)") (class "Default")
      (node (ref "U1") (pin "20") (pinfunction "PA4_20") (pintype "bidirectional"))
    )
    (net (code "57") (name "unconnected-(U1-PA5-Pad21)") (class "Default")
      (node (ref "U1") (pin "21") (pinfunction "PA5_21") (pintype "bidirectional"))
    )
    (net (code "58") (name "unconnected-(U1-PA6-Pad22)") (class "Default")
      (node (ref "U1") (pin "22") (pinfunction "PA6_22") (pintype "bidirectional"))
    )
    (net (code "59") (name "unconnected-(U1-PA7-Pad23)") (class "Default")
      (node (ref "U1") (pin "23") (pinfunction "PA7_23") (pintype "bidirectional"))
    )
    (net (code "60") (name "unconnected-(U1-PA8-Pad41)") (class "Default")
      (node (ref "U1") (pin "41") (pinfunction "PA8_41") (pintype "bidirectional"))
    )
    (net (code "61") (name "unconnected-(U1-PA9-Pad42)") (class "Default")
      (node (ref "U1") (pin "42") (pinfunction "PA9_42") (pintype "bidirectional"))
    )
    (net (code "62") (name "unconnected-(U1-PA10-Pad43)") (class "Default")
      (node (ref "U1") (pin "43") (pinfunction "PA10_43") (pintype "bidirectional"))
    )
    (net (code "63") (name "unconnected-(U1-PA11-Pad44)") (class "Default")
      (node (ref "U1") (pin "44") (pinfunction "PA11_44") (pintype "bidirectional"))
    )
    (net (code "64") (name "unconnected-(U1-PA12-Pad45)") (class "Default")
      (node (ref "U1") (pin "45") (pinfunction "PA12_45") (pintype "bidirectional"))
    )
    (net (code "65") (name "unconnected-(U1-PA15{slash}JTDI-Pad50)") (class "Default")
      (node (ref "U1") (pin "50") (pinfunction "PA15/JTDI_50") (pintype "bidirectional"))
    )
    (net (code "66") (name "unconnected-(U1-PB2{slash}BOOT1-Pad28)") (class "Default")
      (node (ref "U1") (pin "28") (pinfunction "PB2/BOOT1_28") (pintype "bidirectional"))
    )
    (net (code "67") (name "unconnected-(U1-PB3{slash}JTDO-Pad55)") (class "Default")
      (node (ref "U1") (pin "55") (pinfunction "PB3/JTDO_55") (pintype "bidirectional"))
    )
    (net (code "68") (name "unconnected-(U1-PB4{slash}JNTRST-Pad56)") (class "Default")
      (node (ref "U1") (pin "56") (pinfunction "PB4/JNTRST_56") (pintype "bidirectional"))
    )
    (net (code "69") (name "unconnected-(U1-PB5-Pad57)") (class "Default")
      (node (ref "U1") (pin "57") (pinfunction "PB5_57") (pintype "bidirectional"))
    )
    (net (code "70") (name "unconnected-(U1-PB7-Pad59)") (class "Default")
      (node (ref "U1") (pin "59") (pinfunction "PB7_59") (pintype "bidirectional"))
    )
    (net (code "71") (name "unconnected-(U1-PB8-Pad61)") (class "Default")
      (node (ref "U1") (pin "61") (pinfunction "PB8_61") (pintype "bidirectional"))
    )
    (net (code "72") (name "unconnected-(U1-PB9-Pad62)") (class "Default")
      (node (ref "U1") (pin "62") (pinfunction "PB9_62") (pintype "bidirectional"))
    )
    (net (code "73") (name "unconnected-(U1-PB14-Pad35)") (class "Default")
      (node (ref "U1") (pin "35") (pinfunction "PB14_35") (pintype "bidirectional"))
    )
    (net (code "74") (name "unconnected-(U1-PB15-Pad36)") (class "Default")
      (node (ref "U1") (pin "36") (pinfunction "PB15_36") (pintype "bidirectional"))
    )
    (net (code "75") (name "unconnected-(U1-PC0-Pad8)") (class "Default")
      (node (ref "U1") (pin "8") (pinfunction "PC0_8") (pintype "bidirectional"))
    )
    (net (code "76") (name "unconnected-(U1-PC1-Pad9)") (class "Default")
      (node (ref "U1") (pin "9") (pinfunction "PC1_9") (pintype "bidirectional"))
    )
    (net (code "77") (name "unconnected-(U1-PC2-Pad10)") (class "Default")
      (node (ref "U1") (pin "10") (pinfunction "PC2_10") (pintype "bidirectional"))
    )
    (net (code "78") (name "unconnected-(U1-PC3-Pad11)") (class "Default")
      (node (ref "U1") (pin "11") (pinfunction "PC3_11") (pintype "bidirectional"))
    )
    (net (code "79") (name "unconnected-(U1-PC4-Pad24)") (class "Default")
      (node (ref "U1") (pin "24") (pinfunction "PC4_24") (pintype "bidirectional"))
    )
    (net (code "80") (name "unconnected-(U1-PC5-Pad25)") (class "Default")
      (node (ref "U1") (pin "25") (pinfunction "PC5_25") (pintype "bidirectional"))
    )
    (net (code "81") (name "unconnected-(U1-PC6-Pad37)") (class "Default")
      (node (ref "U1") (pin "37") (pinfunction "PC6_37") (pintype "bidirectional"))
    )
    (net (code "82") (name "unconnected-(U1-PC7-Pad38)") (class "Default")
      (node (ref "U1") (pin "38") (pinfunction "PC7_38") (pintype "bidirectional"))
    )
    (net (code "83") (name "unconnected-(U1-PC8-Pad39)") (class "Default")
      (node (ref "U1") (pin "39") (pinfunction "PC8_39") (pintype "bidirectional"))
    )
    (net (code "84") (name "unconnected-(U1-PC9-Pad40)") (class "Default")
      (node (ref "U1") (pin "40") (pinfunction "PC9_40") (pintype "bidirectional"))
    )
    (net (code "85") (name "unconnected-(U1-PC10-Pad51)") (class "Default")
      (node (ref "U1") (pin "51") (pinfunction "PC10_51") (pintype "bidirectional"))
    )
    (net (code "86") (name "unconnected-(U1-PC11-Pad52)") (class "Default")
      (node (ref "U1") (pin "52") (pinfunction "PC11_52") (pintype "bidirectional"))
    )
    (net (code "87") (name "unconnected-(U1-PC12-Pad53)") (class "Default")
      (node (ref "U1") (pin "53") (pinfunction "PC12_53") (pintype "bidirectional"))
    )
    (net (code "88") (name "unconnected-(U1-PC15-OSC32_OUT-Pad4)") (class "Default")
      (node (ref "U1") (pin "4") (pinfunction "PC15-OSC32_OUT_4") (pintype "bidirectional"))
    )
    (net (code "89") (name "unconnected-(U1-PD2-Pad54)") (class "Default")
      (node (ref "U1") (pin "54") (pinfunction "PD2_54") (pintype "bidirectional"))
    )
    (net (code "90") (name "unconnected-(U1-VBAT-Pad1)") (class "Default")
      (node (ref "U1") (pin "1") (pinfunction "VBAT_1") (pintype "power_in"))
    )
    (net (code "91") (name "unconnected-(U4-EN-Pad2)") (class "Default")
      (node (ref "U4") (pin "2") (pinfunction "EN_2") (pintype "passive"))
    )
    (net (code "92") (name "unconnected-(U8-NC-Pad3)") (class "Default")
      (node (ref "U8") (pin "3") (pinfunction "NC_3") (pintype "passive"))
    )
    (net (code "93") (name "unconnected-(U8-NC-Pad4)") (class "Default")
      (node (ref "U8") (pin "4") (pinfunction "NC_4") (pintype "passive"))
    )
  )
)
